# charge_controller_sch.net
KiCad netlist of a schematic drawn in Altium Designer
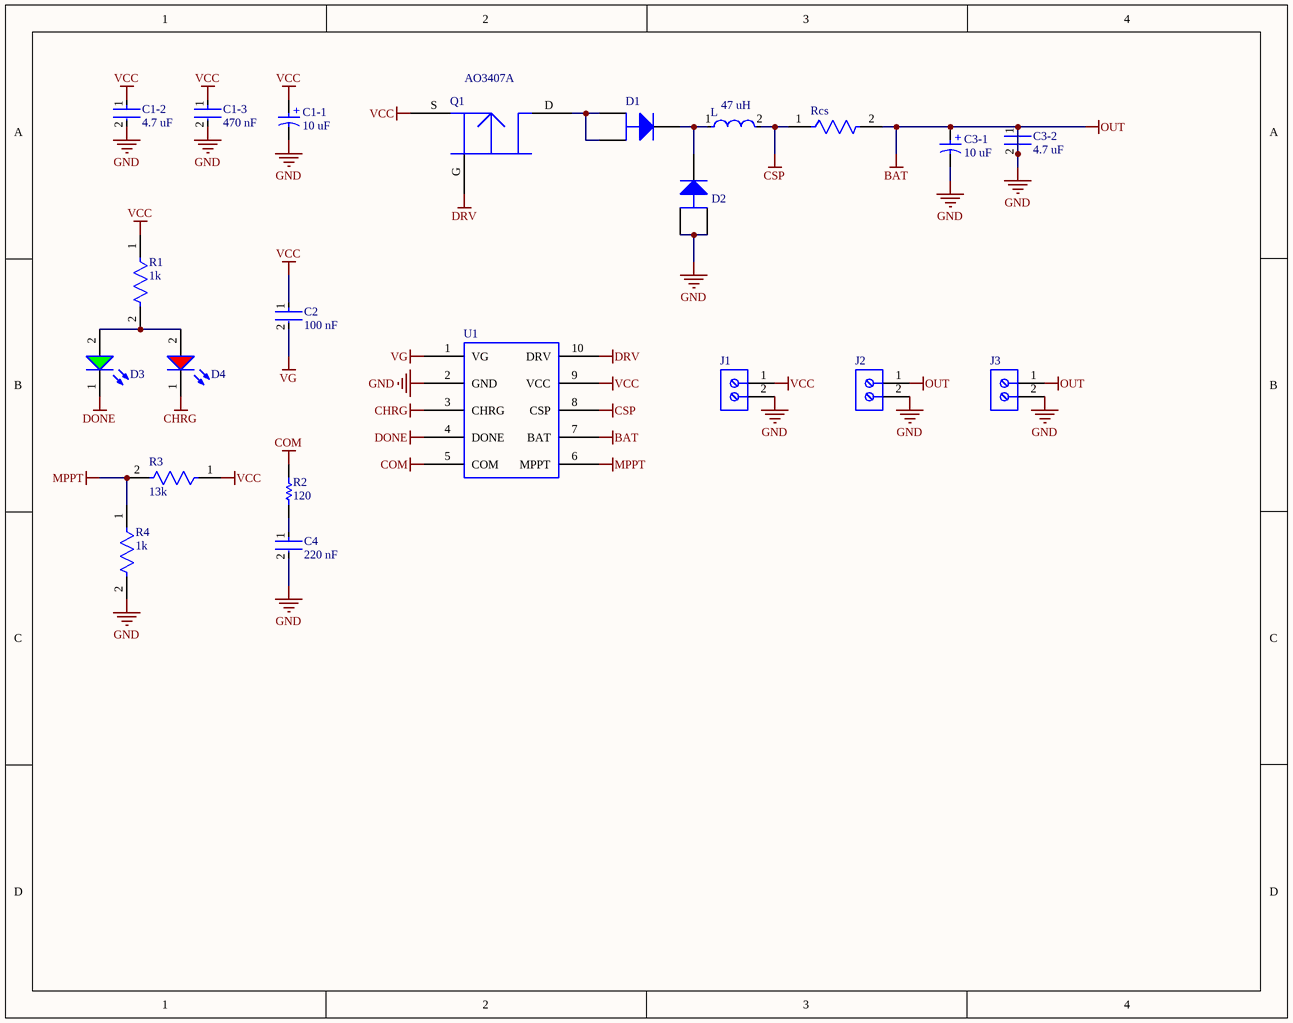
[diagram p0: charge_controller_sch.SchDoc]

(export (version "E")
  (design (tool "Eeschema 10.0.6"))
  (components
    (comp (ref "C1-1")
      (value "10 uF")
      (footprint "WCAP-AS5H_D5H5.5")
      (description "865230542002 WCAP-AS5H Aluminum Electrolytic Capacitors")
      (fields (field (name "TOLERANCE") "20%"))
      (libsource (lib "Altium Content Vault") (part "Capacitor_Polarized"))
    )
    (comp (ref "C1-2")
      (value "4.7 uF")
      (footprint "FP-CL10-IPC_C")
      (description "Cap Ceramic 4.7uF 10V X5R ±10% Pad SMD 0603 +85°C T/R")
      (fields (field (name "TOLERANCE") "10%"))
      (libsource (lib "Altium Content Vault") (part "b4654b650e69147ec39a6b967a45e02"))
    )
    (comp (ref "C1-3")
      (value "470 nF")
      (footprint "FP-GRM21B-0_1-IPC_B")
      (description "Chip Multilayer Ceramic Capacitors for General Purpose, 0805, 0.47uF, X7R, 15%, 10%, 50V")
      (fields (field (name "VOLTAGE") "50V") (field (name "TOLERANCE") "10%"))
      (libsource (lib "Altium Content Vault") (part "b4654b650e69147ec39a6b967a45e02"))
    )
    (comp (ref "C2")
      (value "100 nF")
      (footprint "FP-CC0805-0_85-MFG")
      (description "CAP CER 0.1UF 50V X7R 0805")
      (fields (field (name "TOLERANCE") "0.1") (field (name "MANUFACTURER PART NUMBER") "CC0805KRX7R9BB104"))
      (libsource (lib "Altium Content Vault") (part "11868f565c42a9108669ba33697ecf6"))
    )
    (comp (ref "C3-1")
      (value "10 uF")
      (footprint "WCAP-AS5H_D5H5.5")
      (description "865230542002 WCAP-AS5H Aluminum Electrolytic Capacitors")
      (fields (field (name "TOLERANCE") "20%"))
      (libsource (lib "Altium Content Vault") (part "Capacitor_Polarized"))
    )
    (comp (ref "C3-2")
      (value "4.7 uF")
      (footprint "FP-CL10-IPC_C")
      (description "Cap Ceramic 4.7uF 10V X5R ±10% Pad SMD 0603 +85°C T/R")
      (fields (field (name "TOLERANCE") "10%"))
      (libsource (lib "Altium Content Vault") (part "b4654b650e69147ec39a6b967a45e02"))
    )
    (comp (ref "C4")
      (value "220 nF")
      (footprint "FP-C0805C-DN-MFG")
      (description "CAP CER 0.22UF 50V X7R 0805")
      (fields
        (field (name "MANUFACTURER") "KEMET")
        (field (name "OCTOPART") "https://octopart.com/c0805c224k5ractu-kemet-144670")
      )
      (libsource (lib "Altium Content Vault") (part "b4654b650e69147ec39a6b967a45e02"))
    )
    (comp (ref "D1")
      (value "SS8P3L-M3/86A")
      (footprint "VISH-SS8P3L-TO-277A-3_V")
      (fields (field (name "MANUFACTURER") "Vishay Semiconductor"))
      (libsource (lib "Altium Content Vault") (part "VISH-A1A2K3-3"))
    )
    (comp (ref "D2")
      (value "SS8P3L-M3/86A")
      (footprint "VISH-SS8P3L-TO-277A-3_V")
      (fields (field (name "MANUFACTURER") "Vishay Semiconductor"))
      (libsource (lib "Altium Content Vault") (part "VISH-A1A2K3-3"))
    )
    (comp (ref "D3")
      (value "150060VS75000")
      (footprint "WL-SMCW_0603_150060xx75000")
      (description "WURTH ELEKTRONIK - 150060VS75000 - LED, Green, SMD, 0603, 30 mA, 2 V, 570 nm")
      (libsource (lib "Altium Content Vault") (part "LED_Green_2A-1K"))
    )
    (comp (ref "D4")
      (value "150060RS75000")
      (footprint "WL-SMCW_0603_150060xx75000")
      (description "LED Low-Power Uni-Color Red 630nm 2V 2-Pin Chip 0603(1608Metric) T/R")
      (libsource (lib "Altium Content Vault") (part "LED_Red_2A-1K"))
    )
    (comp (ref "J1")
      (value "691137710002")
      (footprint "691137710002")
      (libsource (lib "Altium Content Vault") (part "TBL - 1R - 02P - Screw"))
    )
    (comp (ref "J2")
      (value "691137710002")
      (footprint "691137710002")
      (libsource (lib "Altium Content Vault") (part "TBL - 1R - 02P - Screw"))
    )
    (comp (ref "J3")
      (value "691137710002")
      (footprint "691137710002")
      (libsource (lib "Altium Content Vault") (part "TBL - 1R - 02P - Screw"))
    )
    (comp (ref "L")
      (value "47 uH")
      (footprint "FP-LB3218-1_8-0_2-IPC_A")
      (description "SMD Inductors 47uH ±10% 0.205A 1.196Ω 1207")
      (fields (field (name "TOLERANCE") "10%"))
      (libsource (lib "Altium Content Vault") (part "725321dda6339637d4d059423bc1c3c"))
    )
    (comp (ref "Q1")
      (value "AO3407A")
      (footprint "AO3407A")
      (libsource (lib "charge_controller_parts") (part "AO3407A"))
    )
    (comp (ref "R1")
      (value "1k")
      (footprint "FP-RR1220-IPC_A")
      (description "1kΩ ±0.5% 0.1W 1/10W Chip Resistor 0805 (2012 Metric) Thin Film")
      (fields (field (name "TOLERANCE") "0.5%"))
      (libsource (lib "Altium Content Vault") (part "1029c3af85768c4190bb7ad29bc67b5"))
    )
    (comp (ref "R2")
      (value "120")
      (footprint "RESC2013X50X40ML20T20")
      (fields (field (name "PART NUMBER") "RG2012N-121-W-T1") (field (name "MANUFACTURER") "Susumu"))
      (libsource (lib "Altium Content Vault") (part "RES"))
    )
    (comp (ref "R3")
      (value "13k")
      (footprint "FP-RMCF0805-MFG")
      (description "13kΩ ±1% 0.125W 0805 Thick Film Chip Resistor AEC-Q200 compliant")
      (fields (field (name "TOLERANCE") "1%"))
      (libsource (lib "Altium Content Vault") (part "1029c3af85768c4190bb7ad29bc67b5"))
    )
    (comp (ref "R4")
      (value "1k")
      (footprint "FP-RR1220-IPC_A")
      (description "1kΩ ±0.5% 0.1W 1/10W Chip Resistor 0805 (2012 Metric) Thin Film")
      (fields (field (name "TOLERANCE") "0.5%"))
      (libsource (lib "Altium Content Vault") (part "1029c3af85768c4190bb7ad29bc67b5"))
    )
    (comp (ref "Rcs")
      (value "CR2512-J/-000ELF")
      (footprint "FP-CR2512-IPC_C")
      (description "Thick Film Chip Resistors 2512 0Ω 1W 5%")
      (fields (field (name "TOLERANCE") "5%"))
      (libsource (lib "Altium Content Vault") (part "1029c3af85768c4190bb7ad29bc67b5"))
    )
    (comp (ref "U1")
      (value "C81968")
      (footprint "CN3767")
      (libsource (lib "charge_controller_parts") (part "CN3767"))
    )
  )
  (nets
    (net (code "1") (name "BAT") (class "Default")
      (node (ref "C1-1") (pin "2") (pinfunction "N_2") (pintype "passive"))
      (node (ref "C1-2") (pin "2") (pinfunction "2_2") (pintype "passive"))
      (node (ref "C1-3") (pin "2") (pinfunction "2_2") (pintype "passive"))
      (node (ref "C3-1") (pin "1") (pinfunction "P_1") (pintype "passive"))
      (node (ref "C3-1") (pin "2") (pinfunction "N_2") (pintype "passive"))
      (node (ref "C3-2") (pin "1") (pinfunction "1_1") (pintype "passive"))
      (node (ref "C3-2") (pin "2") (pinfunction "2_2") (pintype "passive"))
      (node (ref "C4") (pin "2") (pinfunction "2_2") (pintype "passive"))
      (node (ref "D2") (pin "1") (pinfunction "A1_1") (pintype "passive"))
      (node (ref "D2") (pin "2") (pinfunction "A2_2") (pintype "passive"))
      (node (ref "J1") (pin "2") (pinfunction "2_2") (pintype "passive"))
      (node (ref "J2") (pin "1") (pinfunction "1_1") (pintype "passive"))
      (node (ref "J2") (pin "2") (pinfunction "2_2") (pintype "passive"))
      (node (ref "J3") (pin "1") (pinfunction "1_1") (pintype "passive"))
      (node (ref "J3") (pin "2") (pinfunction "2_2") (pintype "passive"))
      (node (ref "R4") (pin "2") (pinfunction "2_2") (pintype "passive"))
      (node (ref "Rcs") (pin "2") (pinfunction "2_2") (pintype "passive"))
      (node (ref "U1") (pin "2") (pinfunction "GND_2") (pintype "passive"))
      (node (ref "U1") (pin "7") (pinfunction "BAT_7") (pintype "passive"))
    )
    (net (code "2") (name "CHRG") (class "Default")
      (node (ref "D4") (pin "1") (pinfunction "K_1") (pintype "passive"))
      (node (ref "U1") (pin "3") (pinfunction "CHRG_3") (pintype "passive"))
    )
    (net (code "3") (name "COM") (class "Default")
      (node (ref "R2") (pin "2") (pinfunction "2_2") (pintype "passive"))
      (node (ref "U1") (pin "5") (pinfunction "COM_5") (pintype "passive"))
    )
    (net (code "4") (name "CSP") (class "Default")
      (node (ref "L") (pin "2") (pinfunction "2_2") (pintype "passive"))
      (node (ref "Rcs") (pin "1") (pinfunction "1_1") (pintype "passive"))
      (node (ref "U1") (pin "8") (pinfunction "CSP_8") (pintype "passive"))
    )
    (net (code "5") (name "DONE") (class "Default")
      (node (ref "D3") (pin "1") (pinfunction "K_1") (pintype "passive"))
      (node (ref "U1") (pin "4") (pinfunction "DONE_4") (pintype "passive"))
    )
    (net (code "6") (name "DRV") (class "Default")
      (node (ref "Q1") (pin "G") (pinfunction "13_G") (pintype "passive"))
      (node (ref "U1") (pin "10") (pinfunction "DRV_10") (pintype "passive"))
    )
    (net (code "7") (name "MPPT") (class "Default")
      (node (ref "R3") (pin "2") (pinfunction "2_2") (pintype "passive"))
      (node (ref "R4") (pin "1") (pinfunction "1_1") (pintype "passive"))
      (node (ref "U1") (pin "6") (pinfunction "MPPT_6") (pintype "passive"))
    )
    (net (code "8") (name "Net-(C4-Pad1)") (class "Default")
      (node (ref "C4") (pin "1") (pinfunction "1_1") (pintype "passive"))
      (node (ref "R2") (pin "1") (pinfunction "1_1") (pintype "passive"))
    )
    (net (code "9") (name "Net-(D1-A1)") (class "Default")
      (node (ref "D1") (pin "1") (pinfunction "A1_1") (pintype "passive"))
      (node (ref "D1") (pin "2") (pinfunction "A2_2") (pintype "passive"))
      (node (ref "Q1") (pin "D") (pinfunction "14_D") (pintype "passive"))
    )
    (net (code "10") (name "Net-(D1-K)") (class "Default")
      (node (ref "D1") (pin "3") (pinfunction "K_3") (pintype "passive"))
      (node (ref "D2") (pin "3") (pinfunction "K_3") (pintype "passive"))
      (node (ref "L") (pin "1") (pinfunction "1_1") (pintype "passive"))
    )
    (net (code "11") (name "Net-(D3-A)") (class "Default")
      (node (ref "D3") (pin "2") (pinfunction "A_2") (pintype "passive"))
      (node (ref "D4") (pin "2") (pinfunction "A_2") (pintype "passive"))
      (node (ref "R1") (pin "2") (pinfunction "2_2") (pintype "passive"))
    )
    (net (code "12") (name "VCC") (class "Default")
      (node (ref "C1-1") (pin "1") (pinfunction "P_1") (pintype "passive"))
      (node (ref "C1-2") (pin "1") (pinfunction "1_1") (pintype "passive"))
      (node (ref "C1-3") (pin "1") (pinfunction "1_1") (pintype "passive"))
      (node (ref "C2") (pin "1") (pinfunction "1_1") (pintype "passive"))
      (node (ref "J1") (pin "1") (pinfunction "1_1") (pintype "passive"))
      (node (ref "Q1") (pin "S") (pinfunction "15_S") (pintype "passive"))
      (node (ref "R1") (pin "1") (pinfunction "1_1") (pintype "passive"))
      (node (ref "R3") (pin "1") (pinfunction "1_1") (pintype "passive"))
      (node (ref "U1") (pin "9") (pinfunction "VCC_9") (pintype "passive"))
    )
    (net (code "13") (name "VG") (class "Default")
      (node (ref "C2") (pin "2") (pinfunction "2_2") (pintype "passive"))
      (node (ref "U1") (pin "1") (pinfunction "VG_1") (pintype "passive"))
    )
  )
)
